# SCH_power.net
KiCad netlist of a schematic drawn in Altium Designer
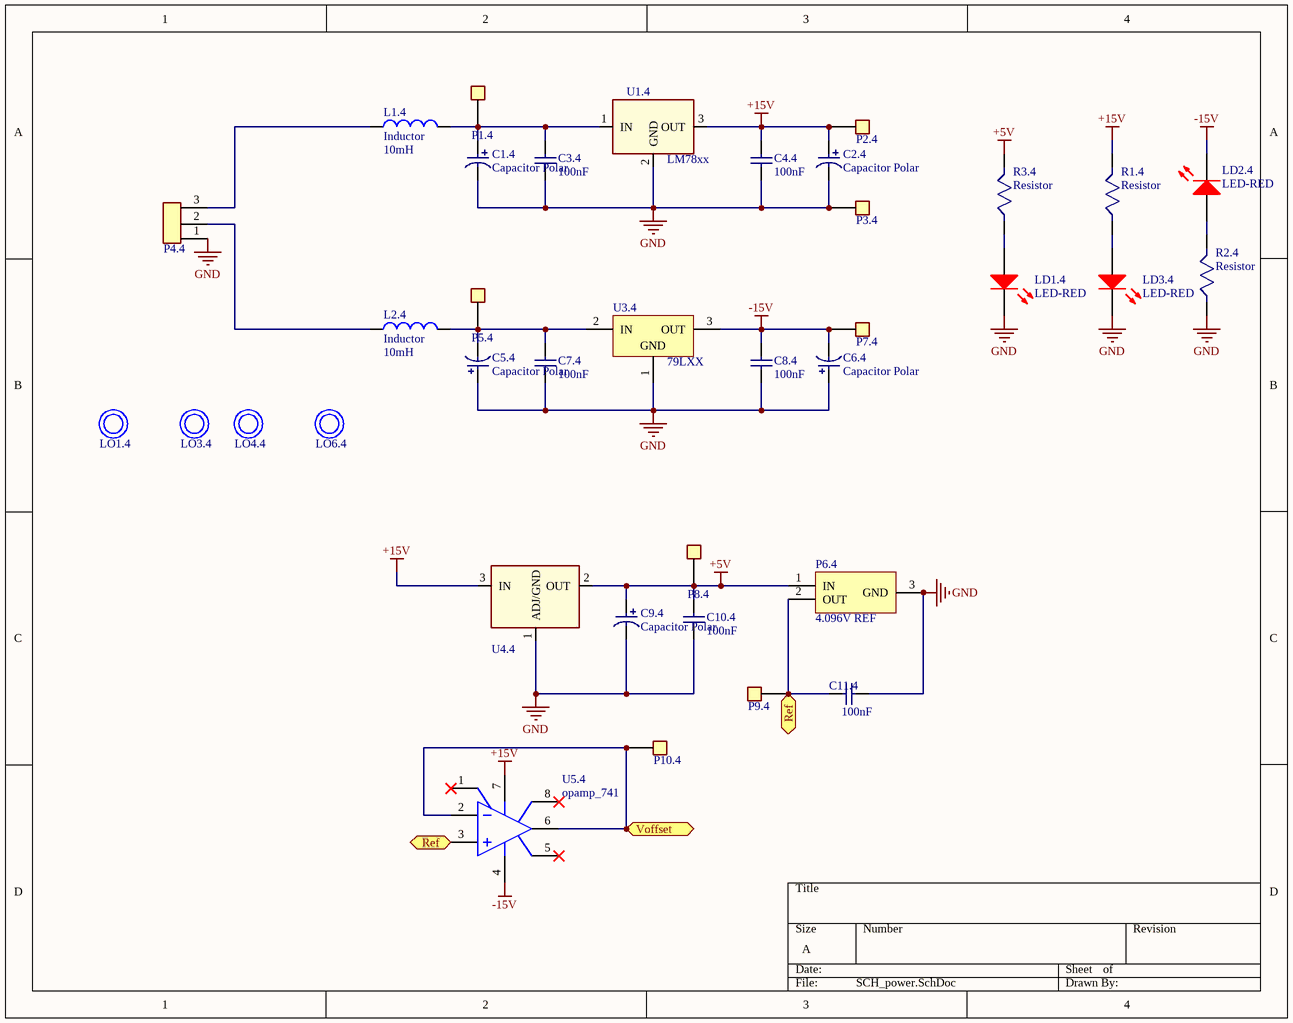
[diagram p0: SCH_power.SchDoc]

(export (version "E")
  (design (tool "Eeschema 10.0.6"))
  (components
    (comp (ref "C1.4")
      (value "Capacitor Polar")
      (footprint "thuvien_altium:CAP_SMD_L=10.5")
      (description "capacitor polar")
      (libsource (lib "thuvien_altium") (part "capacitor_polar 6.3x11mm"))
    )
    (comp (ref "C2.4")
      (value "Capacitor Polar")
      (footprint "thuvien_altium:CAP_SMD_L=10.5")
      (description "capacitor polar")
      (libsource (lib "thuvien_altium") (part "capacitor_polar 6.3x11mm"))
    )
    (comp (ref "C3.4")
      (value "100nF")
      (footprint "thuvien_altium:C-NP-0805")
      (description "capacitor non polar")
      (libsource (lib "thuvien_altium") (part "capacitor_non_polar"))
    )
    (comp (ref "C4.4")
      (value "100nF")
      (footprint "thuvien_altium:C-NP-0805")
      (description "capacitor non polar")
      (libsource (lib "thuvien_altium") (part "capacitor_non_polar"))
    )
    (comp (ref "C5.4")
      (value "Capacitor Polar")
      (footprint "thuvien_altium:CAP_SMD_L=10.5")
      (description "capacitor polar")
      (libsource (lib "thuvien_altium") (part "capacitor_polar 6.3x11mm"))
    )
    (comp (ref "C6.4")
      (value "Capacitor Polar")
      (footprint "thuvien_altium:CAP_SMD_L=10.5")
      (description "capacitor polar")
      (libsource (lib "thuvien_altium") (part "capacitor_polar 6.3x11mm"))
    )
    (comp (ref "C7.4")
      (value "100nF")
      (footprint "thuvien_altium:C-NP-0805")
      (description "capacitor non polar")
      (libsource (lib "thuvien_altium") (part "capacitor_non_polar"))
    )
    (comp (ref "C8.4")
      (value "100nF")
      (footprint "thuvien_altium:C-NP-0805")
      (description "capacitor non polar")
      (libsource (lib "thuvien_altium") (part "capacitor_non_polar"))
    )
    (comp (ref "C9.4")
      (value "Capacitor Polar")
      (footprint "thuvien_altium:CAP_SMD_L=10.5")
      (description "capacitor polar")
      (libsource (lib "thuvien_altium") (part "capacitor_polar 6.3x11mm"))
    )
    (comp (ref "C10.4")
      (value "100nF")
      (footprint "thuvien_altium:C-NP-0805")
      (description "capacitor non polar")
      (libsource (lib "thuvien_altium") (part "capacitor_non_polar"))
    )
    (comp (ref "C11.4")
      (value "100nF")
      (footprint "thuvien_altium:C-NP-0805")
      (description "capacitor non polar")
      (libsource (lib "thuvien_altium") (part "capacitor_non_polar"))
    )
    (comp (ref "L1.4")
      (value "Inductor")
      (footprint "thuvien_altium:induction_coil")
      (fields (field (name "ALTIUM_VALUE") "10mH") (field (name "PUBLISHER") "Altium Limited"))
      (libsource (lib "thuvien_altium") (part "Inductor"))
    )
    (comp (ref "L2.4")
      (value "Inductor")
      (footprint "thuvien_altium:induction_coil")
      (fields (field (name "ALTIUM_VALUE") "10mH") (field (name "PUBLISHER") "Altium Limited"))
      (libsource (lib "thuvien_altium") (part "Inductor"))
    )
    (comp (ref "LD1.4")
      (value "LED-RED")
      (footprint "thuvien_altium:SMD 1206 RED")
      (description "LED RED CLEAR 0603 SMD")
      (fields
        (field (name "MANUFACTURER") "Lite-On Inc.")
        (field (name "MANUFACTURER PART NUMBER") "LTST-C191KRKT")
      )
      (libsource (lib "thuvien_altium") (part "LED_LTST-C191KRKT"))
    )
    (comp (ref "LD2.4")
      (value "LED-RED")
      (footprint "thuvien_altium:SMD 1206 RED")
      (description "LED RED CLEAR 0603 SMD")
      (fields
        (field (name "MANUFACTURER") "Lite-On Inc.")
        (field (name "MANUFACTURER PART NUMBER") "LTST-C191KRKT")
      )
      (libsource (lib "thuvien_altium") (part "LED_LTST-C191KRKT"))
    )
    (comp (ref "LD3.4")
      (value "LED-RED")
      (footprint "thuvien_altium:SMD 1206 RED")
      (description "LED RED CLEAR 0603 SMD")
      (fields
        (field (name "MANUFACTURER") "Lite-On Inc.")
        (field (name "MANUFACTURER PART NUMBER") "LTST-C191KRKT")
      )
      (libsource (lib "thuvien_altium") (part "LED_LTST-C191KRKT"))
    )
    (comp (ref "LO1.4")
      (value "LO KHOAN")
      (footprint "thuvien_altium:SP PCB")
      (libsource (lib "thuvien_altium") (part "LO KHOAN"))
    )
    (comp (ref "LO3.4")
      (value "LO KHOAN")
      (footprint "thuvien_altium:SP PCB")
      (libsource (lib "thuvien_altium") (part "LO KHOAN"))
    )
    (comp (ref "LO4.4")
      (value "LO KHOAN")
      (footprint "thuvien_altium:SP PCB")
      (libsource (lib "thuvien_altium") (part "LO KHOAN"))
    )
    (comp (ref "LO6.4")
      (value "LO KHOAN")
      (footprint "thuvien_altium:SP PCB")
      (libsource (lib "thuvien_altium") (part "LO KHOAN"))
    )
    (comp (ref "P1.4")
      (value "testpin")
      (footprint "thuvien_altium:tp_red_1p")
      (libsource (lib "") (part "testpin_1"))
    )
    (comp (ref "P2.4")
      (value "testpin")
      (footprint "thuvien_altium:tp_red_1p")
      (libsource (lib "") (part "testpin_2"))
    )
    (comp (ref "P3.4")
      (value "testpin")
      (footprint "thuvien_altium:Tp_black_1p")
      (libsource (lib "") (part "testpin_2"))
    )
    (comp (ref "P4.4")
      (value "domino_3p")
      (footprint "thuvien_altium:domino_3p")
      (libsource (lib "thuvien_altium") (part "domino_3p"))
    )
    (comp (ref "P5.4")
      (value "testpin")
      (footprint "thuvien_altium:tp_red_1p")
      (libsource (lib "") (part "testpin_1"))
    )
    (comp (ref "P6.4")
      (value "4.096V REF")
      (footprint "thuvien_altium:SOT233")
      (libsource (lib "thuvien_altium") (part "MCP1541T"))
    )
    (comp (ref "P7.4")
      (value "testpin")
      (footprint "thuvien_altium:tp_red_1p")
      (libsource (lib "") (part "testpin_2"))
    )
    (comp (ref "P8.4")
      (value "testpin")
      (footprint "thuvien_altium:tp_red_1p")
      (libsource (lib "") (part "testpin_1"))
    )
    (comp (ref "P9.4")
      (value "testpin")
      (footprint "thuvien_altium:tp_red_1p")
      (libsource (lib "thuvien_altium") (part "testpin"))
    )
    (comp (ref "P10.4")
      (value "testpin")
      (footprint "thuvien_altium:tp_red_1p")
      (libsource (lib "") (part "testpin_2"))
    )
    (comp (ref "R1.4")
      (value "Resistor")
      (footprint "RESC0805")
      (description "resistor")
      (libsource (lib "thuvien_altium") (part "resistor"))
    )
    (comp (ref "R2.4")
      (value "Resistor")
      (footprint "RESC0805")
      (description "resistor")
      (libsource (lib "thuvien_altium") (part "resistor"))
    )
    (comp (ref "R3.4")
      (value "Resistor")
      (footprint "RESC0805")
      (description "resistor")
      (libsource (lib "thuvien_altium") (part "resistor"))
    )
    (comp (ref "U1.4")
      (value "LM78xx")
      (footprint "thuvien_altium:TO 220 THermal 25x25")
      (description "Regulator")
      (fields
        (field (name "MANUFACTURER") "Fairchild Semiconductor Corporation")
        (field (name "TOLERANCE") "4 %")
        (field (name "PUBLISHER") "Hoang Nguyen")
      )
      (libsource (lib "thuvien_altium") (part "LM78xx"))
    )
    (comp (ref "U3.4")
      (value "79LXX")
      (footprint "thuvien_altium:TO 220 THermal 25x25")
      (description "3-Terminal Negative Regulator")
      (fields (field (name "PUBLISHER") "Altium Limited"))
      (libsource (lib "thuvien_altium") (part "LM79LXX"))
    )
    (comp (ref "U4.4")
      (value "LM1117MP-3.3TR")
      (footprint "thuvien_altium:AMS1117")
      (description "3.3V 800mA Low-Dropout Linear Regulator")
      (fields (field (name "PUBLISHER") "Hoang Nguyen"))
      (libsource (lib "thuvien_altium") (part "LM1117MP-3.3TR"))
    )
    (comp (ref "U5.4")
      (value "opamp_741")
      (footprint "thuvien_altium:SOIC-8_dan")
      (libsource (lib "thuvien_altium") (part "opamp 741"))
    )
  )
  (nets
    (net (code "1") (name "+5V") (class "Default")
      (node (ref "C10.4") (pin "1") (pinfunction "1_1") (pintype "power_in"))
      (node (ref "C9.4") (pin "1") (pinfunction "1_1") (pintype "power_in"))
      (node (ref "P6.4") (pin "1") (pinfunction "IN_1") (pintype "passive"))
      (node (ref "P8.4") (pin "1") (pinfunction "1_1") (pintype "power_in"))
      (node (ref "R3.4") (pin "2") (pinfunction "2_2") (pintype "power_in"))
      (node (ref "U4.4") (pin "2") (pinfunction "OUT_2") (pintype "power_in"))
    )
    (net (code "2") (name "+15V") (class "Default")
      (node (ref "C2.4") (pin "1") (pinfunction "1_1") (pintype "power_in"))
      (node (ref "C4.4") (pin "1") (pinfunction "1_1") (pintype "power_in"))
      (node (ref "P2.4") (pin "1") (pinfunction "1_1") (pintype "power_in"))
      (node (ref "R1.4") (pin "2") (pinfunction "2_2") (pintype "power_in"))
      (node (ref "U1.4") (pin "3") (pinfunction "OUT_3") (pintype "power_in"))
      (node (ref "U4.4") (pin "3") (pinfunction "IN_3") (pintype "power_in"))
      (node (ref "U5.4") (pin "7") (pinfunction "V+_7") (pintype "power_in"))
    )
    (net (code "3") (name "-15V") (class "Default")
      (node (ref "C6.4") (pin "2") (pinfunction "2_2") (pintype "power_in"))
      (node (ref "C8.4") (pin "1") (pinfunction "1_1") (pintype "power_in"))
      (node (ref "LD2.4") (pin "2") (pinfunction "K_2") (pintype "passive"))
      (node (ref "P7.4") (pin "1") (pinfunction "1_1") (pintype "power_in"))
      (node (ref "U3.4") (pin "3") (pinfunction "OUT_3") (pintype "power_in"))
      (node (ref "U5.4") (pin "4") (pinfunction "V-_4") (pintype "power_in"))
    )
    (net (code "4") (name "/Ref") (class "Default")
      (node (ref "C11.4") (pin "2") (pinfunction "2_2") (pintype "power_in"))
      (node (ref "P6.4") (pin "2") (pinfunction "OUT_2") (pintype "passive"))
      (node (ref "P9.4") (pin "1") (pinfunction "1_1") (pintype "power_in"))
      (node (ref "U5.4") (pin "3") (pinfunction "IN+_3") (pintype "power_in"))
    )
    (net (code "5") (name "/Voffset") (class "Default")
      (node (ref "P10.4") (pin "1") (pinfunction "1_1") (pintype "power_in"))
      (node (ref "U5.4") (pin "2") (pinfunction "IN-_2") (pintype "power_in"))
      (node (ref "U5.4") (pin "6") (pinfunction "OUT_6") (pintype "power_in"))
    )
    (net (code "6") (name "GND") (class "Default")
      (node (ref "C1.4") (pin "2") (pinfunction "2_2") (pintype "power_in"))
      (node (ref "C10.4") (pin "2") (pinfunction "2_2") (pintype "power_in"))
      (node (ref "C11.4") (pin "1") (pinfunction "1_1") (pintype "power_in"))
      (node (ref "C2.4") (pin "2") (pinfunction "2_2") (pintype "power_in"))
      (node (ref "C3.4") (pin "2") (pinfunction "2_2") (pintype "power_in"))
      (node (ref "C4.4") (pin "2") (pinfunction "2_2") (pintype "power_in"))
      (node (ref "C5.4") (pin "1") (pinfunction "1_1") (pintype "power_in"))
      (node (ref "C6.4") (pin "1") (pinfunction "1_1") (pintype "power_in"))
      (node (ref "C7.4") (pin "2") (pinfunction "2_2") (pintype "power_in"))
      (node (ref "C8.4") (pin "2") (pinfunction "2_2") (pintype "power_in"))
      (node (ref "C9.4") (pin "2") (pinfunction "2_2") (pintype "power_in"))
      (node (ref "LD1.4") (pin "2") (pinfunction "K_2") (pintype "passive"))
      (node (ref "LD3.4") (pin "2") (pinfunction "K_2") (pintype "passive"))
      (node (ref "P3.4") (pin "1") (pinfunction "1_1") (pintype "power_in"))
      (node (ref "P4.4") (pin "1") (pinfunction "1_1") (pintype "passive"))
      (node (ref "P6.4") (pin "3") (pinfunction "GND_3") (pintype "passive"))
      (node (ref "R2.4") (pin "1") (pinfunction "1_1") (pintype "power_in"))
      (node (ref "U1.4") (pin "2") (pinfunction "GND_2") (pintype "power_in"))
      (node (ref "U3.4") (pin "1") (pinfunction "GND_1") (pintype "power_in"))
      (node (ref "U4.4") (pin "1") (pinfunction "ADJ/GND_1") (pintype "power_in"))
    )
    (net (code "7") (name "Net-(L1.4-Pad1)") (class "Default")
      (node (ref "L1.4") (pin "1") (pinfunction "1_1") (pintype "passive"))
      (node (ref "P4.4") (pin "3") (pinfunction "3_3") (pintype "passive"))
    )
    (net (code "8") (name "Net-(L2.4-Pad1)") (class "Default")
      (node (ref "L2.4") (pin "1") (pinfunction "1_1") (pintype "passive"))
      (node (ref "P4.4") (pin "2") (pinfunction "2_2") (pintype "passive"))
    )
    (net (code "9") (name "Net-(LD1.4-A)") (class "Default")
      (node (ref "LD1.4") (pin "1") (pinfunction "A_1") (pintype "passive"))
      (node (ref "R3.4") (pin "1") (pinfunction "1_1") (pintype "power_in"))
    )
    (net (code "10") (name "Net-(LD2.4-A)") (class "Default")
      (node (ref "LD2.4") (pin "1") (pinfunction "A_1") (pintype "passive"))
      (node (ref "R2.4") (pin "2") (pinfunction "2_2") (pintype "power_in"))
    )
    (net (code "11") (name "Net-(LD3.4-A)") (class "Default")
      (node (ref "LD3.4") (pin "1") (pinfunction "A_1") (pintype "passive"))
      (node (ref "R1.4") (pin "1") (pinfunction "1_1") (pintype "power_in"))
    )
    (net (code "12") (name "Net-(U1.4-IN)") (class "Default")
      (node (ref "C1.4") (pin "1") (pinfunction "1_1") (pintype "power_in"))
      (node (ref "C3.4") (pin "1") (pinfunction "1_1") (pintype "power_in"))
      (node (ref "L1.4") (pin "2") (pinfunction "2_2") (pintype "passive"))
      (node (ref "P1.4") (pin "1") (pinfunction "1_1") (pintype "power_in"))
      (node (ref "U1.4") (pin "1") (pinfunction "IN_1") (pintype "power_in"))
    )
    (net (code "13") (name "Net-(U3.4-IN)") (class "Default")
      (node (ref "C5.4") (pin "2") (pinfunction "2_2") (pintype "power_in"))
      (node (ref "C7.4") (pin "1") (pinfunction "1_1") (pintype "power_in"))
      (node (ref "L2.4") (pin "2") (pinfunction "2_2") (pintype "passive"))
      (node (ref "P5.4") (pin "1") (pinfunction "1_1") (pintype "power_in"))
      (node (ref "U3.4") (pin "2") (pinfunction "IN_2") (pintype "power_in"))
    )
    (net (code "14") (name "unconnected-(U5.4-NC-Pad5)") (class "Default")
      (node (ref "U5.4") (pin "5") (pinfunction "NC_5") (pintype "passive+no_connect"))
    )
    (net (code "15") (name "unconnected-(U5.4-VOSTRIM-Pad1)") (class "Default")
      (node (ref "U5.4") (pin "1") (pinfunction "VOSTRIM_1") (pintype "passive+no_connect"))
    )
    (net (code "16") (name "unconnected-(U5.4-VOSTRIM-Pad8)") (class "Default")
      (node (ref "U5.4") (pin "8") (pinfunction "VOSTRIM_8") (pintype "passive+no_connect"))
    )
  )
)
